# CAN_PHY.net
KiCad netlist of a schematic drawn in Altium Designer
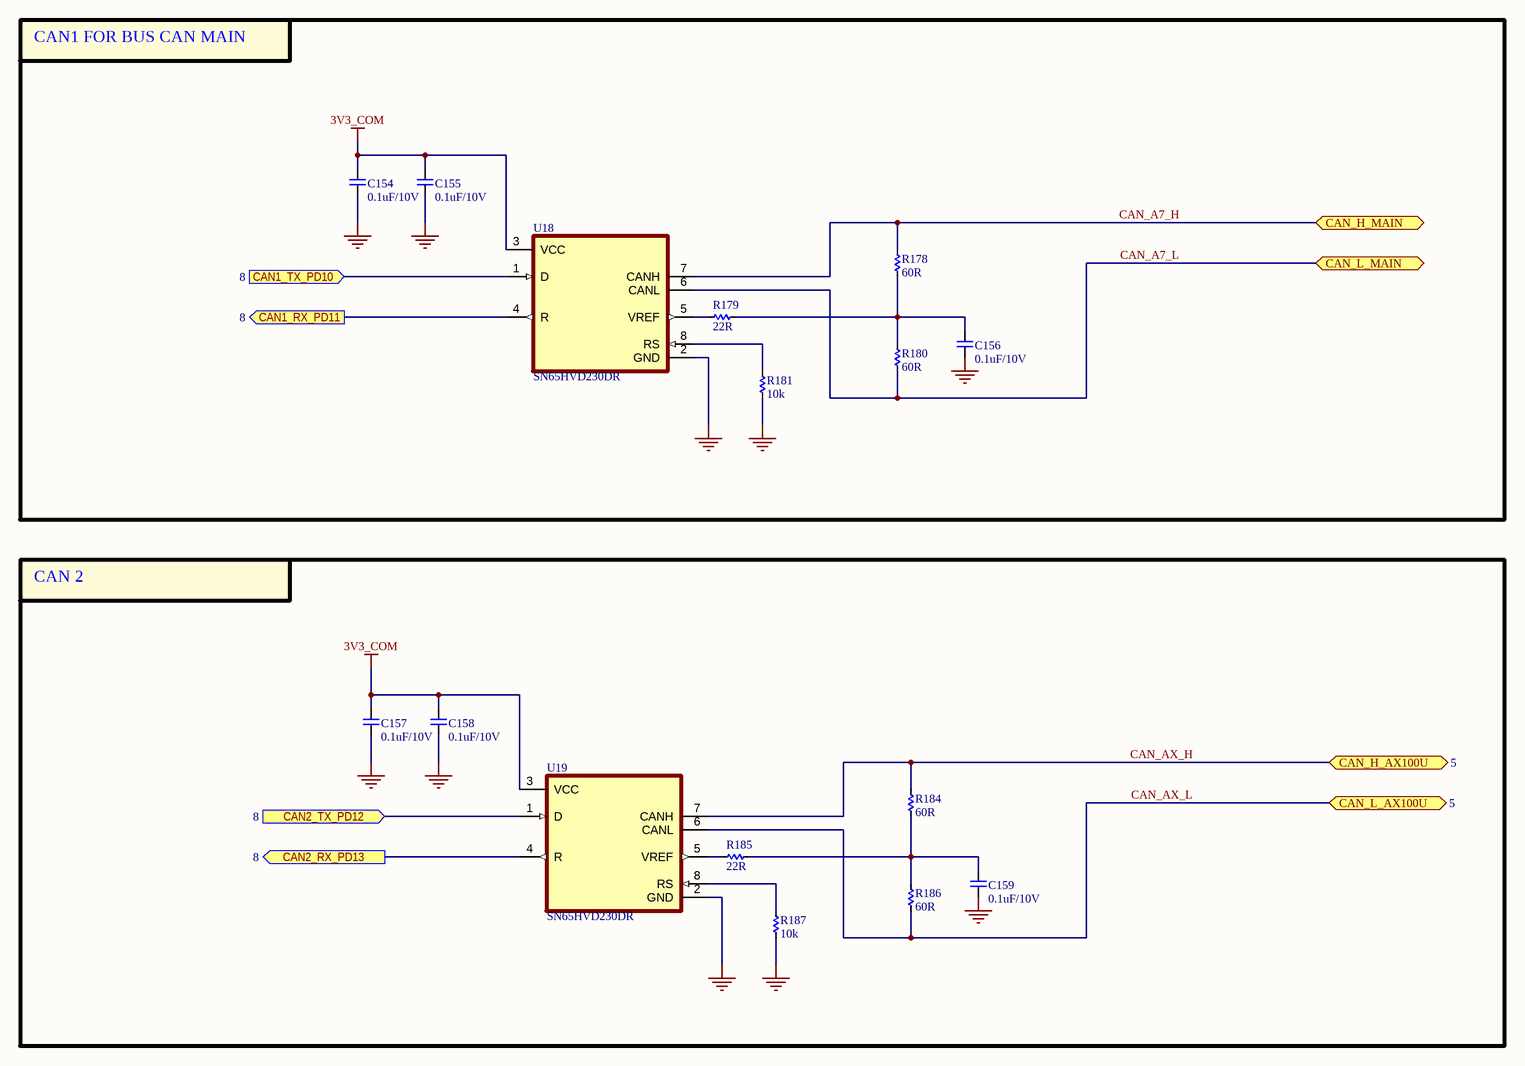
[diagram p0: CAN_PHY.SchDoc]

(export (version "E")
  (design (tool "Eeschema 10.0.6"))
  (components
    (comp (ref "C154")
      (value "0.1uF/10V")
      (footprint "CAP_C_1005X50_L")
      (description "CAP CHIP")
      (libsource (lib "IFBschelib") (part "_CAP_C_2"))
    )
    (comp (ref "C155")
      (value "0.1uF/10V")
      (footprint "CAP_C_1005X50_L")
      (description "CAP CHIP")
      (libsource (lib "IFBschelib") (part "_CAP_C_2"))
    )
    (comp (ref "C156")
      (value "0.1uF/10V")
      (footprint "CAP_C_1005X50_L")
      (description "CAP CHIP")
      (libsource (lib "IFBschelib") (part "_CAP_C_2"))
    )
    (comp (ref "C157")
      (value "0.1uF/10V")
      (footprint "CAP_C_1005X50_L")
      (description "CAP CHIP")
      (libsource (lib "IFBschelib") (part "_CAP_C_2"))
    )
    (comp (ref "C158")
      (value "0.1uF/10V")
      (footprint "CAP_C_1005X50_L")
      (description "CAP CHIP")
      (libsource (lib "IFBschelib") (part "_CAP_C_2"))
    )
    (comp (ref "C159")
      (value "0.1uF/10V")
      (footprint "CAP_C_1005X50_L")
      (description "CAP CHIP")
      (libsource (lib "IFBschelib") (part "_CAP_C_2"))
    )
    (comp (ref "R178")
      (value "60R")
      (footprint "RES_C_1005x30_L")
      (description "RES")
      (libsource (lib "IFBschelib") (part "_RES_B_2"))
    )
    (comp (ref "R179")
      (value "22R")
      (footprint "RES_C_1005x30_L")
      (description "RES")
      (libsource (lib "IFBschelib") (part "_RES_B_2"))
    )
    (comp (ref "R180")
      (value "60R")
      (footprint "RES_C_1005x30_L")
      (description "RES")
      (libsource (lib "IFBschelib") (part "_RES_B_2"))
    )
    (comp (ref "R181")
      (value "10k")
      (footprint "RES_C_1005x30_L")
      (description "RES")
      (libsource (lib "IFBschelib") (part "_RES_B_2"))
    )
    (comp (ref "R184")
      (value "60R")
      (footprint "RES_C_1005x30_L")
      (description "RES")
      (libsource (lib "IFBschelib") (part "_RES_B_2"))
    )
    (comp (ref "R185")
      (value "22R")
      (footprint "RES_C_1005x30_L")
      (description "RES")
      (libsource (lib "IFBschelib") (part "_RES_B_2"))
    )
    (comp (ref "R186")
      (value "60R")
      (footprint "RES_C_1005x30_L")
      (description "RES")
      (libsource (lib "IFBschelib") (part "_RES_B_2"))
    )
    (comp (ref "R187")
      (value "10k")
      (footprint "RES_C_1005x30_L")
      (description "RES")
      (libsource (lib "IFBschelib") (part "_RES_B_2"))
    )
    (comp (ref "U18")
      (value "SN65HVD230DR")
      (footprint "SOIC127P599X175-8N")
      (description "3.3 V CAN Transceiver with Standby Mode")
      (fields (field (name "MF") "Texas Instruments"))
      (libsource (lib "IFBschelib") (part "SN65HVD230DR"))
    )
    (comp (ref "U19")
      (value "SN65HVD230DR")
      (footprint "SOIC127P599X175-8N")
      (description "3.3 V CAN Transceiver with Standby Mode")
      (fields (field (name "MF") "Texas Instruments"))
      (libsource (lib "IFBschelib") (part "SN65HVD230DR"))
    )
  )
  (nets
    (net (code "1") (name "/CAN1_RX_PD11") (class "Default")
      (node (ref "U18") (pin "4") (pinfunction "R_4") (pintype "output"))
    )
    (net (code "2") (name "/CAN1_TX_PD10") (class "Default")
      (node (ref "U18") (pin "1") (pinfunction "D_1") (pintype "input"))
    )
    (net (code "3") (name "/CAN2_RX_PD13") (class "Default")
      (node (ref "U19") (pin "4") (pinfunction "R_4") (pintype "output"))
    )
    (net (code "4") (name "/CAN2_TX_PD12") (class "Default")
      (node (ref "U19") (pin "1") (pinfunction "D_1") (pintype "input"))
    )
    (net (code "5") (name "/CAN_A7_H") (class "Default")
      (node (ref "R178") (pin "1") (pinfunction "1_1") (pintype "passive"))
      (node (ref "U18") (pin "7") (pinfunction "CANH_7") (pintype "passive"))
    )
    (net (code "6") (name "/CAN_A7_L") (class "Default")
      (node (ref "R180") (pin "2") (pinfunction "2_2") (pintype "passive"))
      (node (ref "U18") (pin "6") (pinfunction "CANL_6") (pintype "passive"))
    )
    (net (code "7") (name "/CAN_AX_H") (class "Default")
      (node (ref "R184") (pin "1") (pinfunction "1_1") (pintype "passive"))
      (node (ref "U19") (pin "7") (pinfunction "CANH_7") (pintype "passive"))
    )
    (net (code "8") (name "/CAN_AX_L") (class "Default")
      (node (ref "R186") (pin "2") (pinfunction "2_2") (pintype "passive"))
      (node (ref "U19") (pin "6") (pinfunction "CANL_6") (pintype "passive"))
    )
    (net (code "9") (name "3V3_COM") (class "Default")
      (node (ref "C154") (pin "2") (pinfunction "2_2") (pintype "passive"))
      (node (ref "C155") (pin "2") (pinfunction "2_2") (pintype "passive"))
      (node (ref "C157") (pin "2") (pinfunction "2_2") (pintype "passive"))
      (node (ref "C158") (pin "2") (pinfunction "2_2") (pintype "passive"))
      (node (ref "U18") (pin "3") (pinfunction "VCC_3") (pintype "power_in"))
      (node (ref "U19") (pin "3") (pinfunction "VCC_3") (pintype "power_in"))
    )
    (net (code "10") (name "GND") (class "Default")
      (node (ref "C154") (pin "1") (pinfunction "1_1") (pintype "passive"))
      (node (ref "C155") (pin "1") (pinfunction "1_1") (pintype "passive"))
      (node (ref "C156") (pin "1") (pinfunction "1_1") (pintype "passive"))
      (node (ref "C157") (pin "1") (pinfunction "1_1") (pintype "passive"))
      (node (ref "C158") (pin "1") (pinfunction "1_1") (pintype "passive"))
      (node (ref "C159") (pin "1") (pinfunction "1_1") (pintype "passive"))
      (node (ref "R181") (pin "2") (pinfunction "2_2") (pintype "passive"))
      (node (ref "R187") (pin "2") (pinfunction "2_2") (pintype "passive"))
      (node (ref "U18") (pin "2") (pinfunction "GND_2") (pintype "power_in"))
      (node (ref "U19") (pin "2") (pinfunction "GND_2") (pintype "power_in"))
    )
    (net (code "11") (name "Net-(C156-Pad2)") (class "Default")
      (node (ref "C156") (pin "2") (pinfunction "2_2") (pintype "passive"))
      (node (ref "R178") (pin "2") (pinfunction "2_2") (pintype "passive"))
      (node (ref "R179") (pin "1") (pinfunction "1_1") (pintype "passive"))
      (node (ref "R180") (pin "1") (pinfunction "1_1") (pintype "passive"))
    )
    (net (code "12") (name "Net-(C159-Pad2)") (class "Default")
      (node (ref "C159") (pin "2") (pinfunction "2_2") (pintype "passive"))
      (node (ref "R184") (pin "2") (pinfunction "2_2") (pintype "passive"))
      (node (ref "R185") (pin "1") (pinfunction "1_1") (pintype "passive"))
      (node (ref "R186") (pin "1") (pinfunction "1_1") (pintype "passive"))
    )
    (net (code "13") (name "Net-(U18-RS)") (class "Default")
      (node (ref "R181") (pin "1") (pinfunction "1_1") (pintype "passive"))
      (node (ref "U18") (pin "8") (pinfunction "RS_8") (pintype "input"))
    )
    (net (code "14") (name "Net-(U18-VREF)") (class "Default")
      (node (ref "R179") (pin "2") (pinfunction "2_2") (pintype "passive"))
      (node (ref "U18") (pin "5") (pinfunction "VREF_5") (pintype "output"))
    )
    (net (code "15") (name "Net-(U19-RS)") (class "Default")
      (node (ref "R187") (pin "1") (pinfunction "1_1") (pintype "passive"))
      (node (ref "U19") (pin "8") (pinfunction "RS_8") (pintype "input"))
    )
    (net (code "16") (name "Net-(U19-VREF)") (class "Default")
      (node (ref "R185") (pin "2") (pinfunction "2_2") (pintype "passive"))
      (node (ref "U19") (pin "5") (pinfunction "VREF_5") (pintype "output"))
    )
  )
)
